# MC33797.net
KiCad netlist of a schematic drawn in Altium Designer
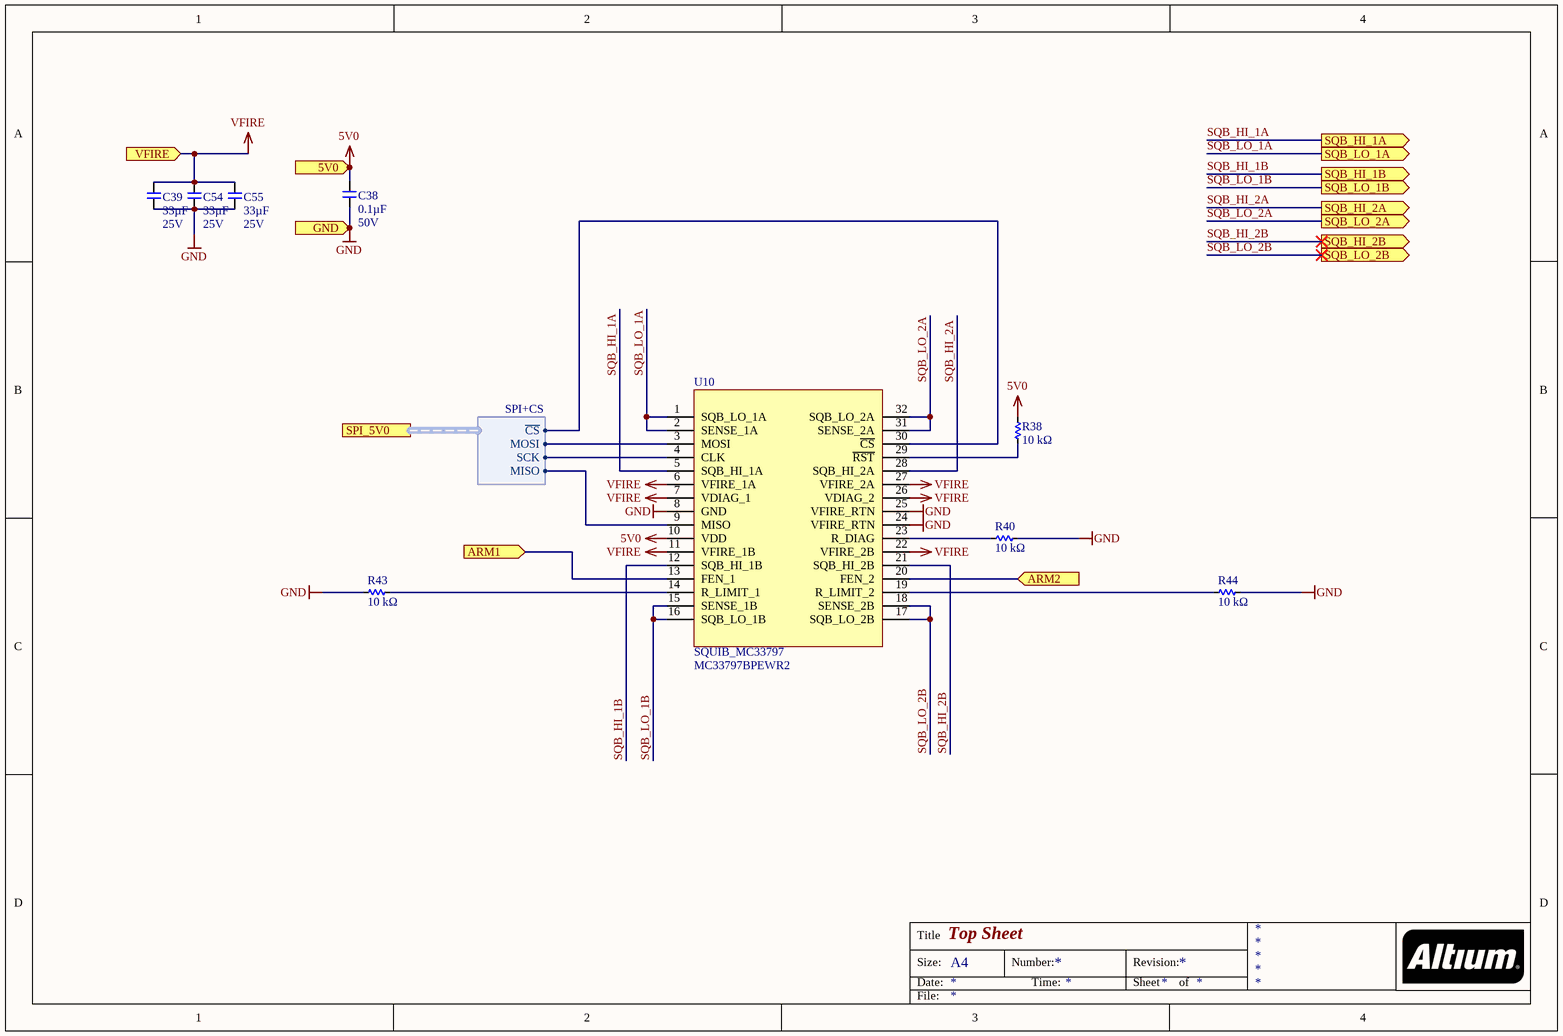
[diagram p0: MC33797.SchDoc]

(export (version "E")
  (design (tool "Eeschema 10.0.6"))
  (components
    (comp (ref "C38")
      (value "__template_cap")
      (footprint "C0603")
      (fields
        (field (name "CAPACITANCE (SHORTHAND)") "0.1µF")
        (field (name "RATED VOLTAGE") "50V")
        (field (name "MANUFACTURER") "Murata Electronics North America")
      )
      (libsource (lib "passives") (part "__template_cap"))
    )
    (comp (ref "C39")
      (value "CAP_33UF_1206_SMD")
      (footprint "C1206")
      (description "100UF SMD CAP CERAMIC")
      (fields
        (field (name "MANUFACTURER") "Murata Electronics North America")
        (field (name "MANUFACTURER PART NUMBER") "GRM31CD80J107ME39L")
        (field (name "CAPACITANCE") "33µF")
        (field (name "VOLTAGE - RATED") "25V")
      )
      (libsource (lib "SSI") (part "CAP_100UF_1206_SMD"))
    )
    (comp (ref "C54")
      (value "CAP_33UF_1206_SMD")
      (footprint "C1206")
      (description "100UF SMD CAP CERAMIC")
      (fields
        (field (name "MANUFACTURER") "Murata Electronics North America")
        (field (name "MANUFACTURER PART NUMBER") "GRM31CD80J107ME39L")
        (field (name "CAPACITANCE") "33µF")
        (field (name "VOLTAGE - RATED") "25V")
      )
      (libsource (lib "SSI") (part "CAP_100UF_1206_SMD"))
    )
    (comp (ref "C55")
      (value "CAP_33UF_1206_SMD")
      (footprint "C1206")
      (description "100UF SMD CAP CERAMIC")
      (fields
        (field (name "MANUFACTURER") "Murata Electronics North America")
        (field (name "MANUFACTURER PART NUMBER") "GRM31CD80J107ME39L")
        (field (name "CAPACITANCE") "33µF")
        (field (name "VOLTAGE - RATED") "25V")
      )
      (libsource (lib "SSI") (part "CAP_100UF_1206_SMD"))
    )
    (comp (ref "R38")
      (value "__template_resistor")
      (footprint "R0603")
      (fields
        (field (name "RESISTANCE") "10 kΩ")
        (field (name "MANUFACTURER PART NUMBER") "RC0603FR-0710KL")
        (field (name "MANUFACTURER") "Yageo")
        (field (name "TOLERANCE") "±1%")
      )
      (libsource (lib "passives") (part "__template_resistor"))
    )
    (comp (ref "R40")
      (value "__template_resistor")
      (footprint "R0603")
      (fields
        (field (name "RESISTANCE") "10 kΩ")
        (field (name "MANUFACTURER PART NUMBER") "RC0603FR-0710KL")
        (field (name "MANUFACTURER") "Yageo")
        (field (name "TOLERANCE") "±1%")
      )
      (libsource (lib "passives") (part "__template_resistor"))
    )
    (comp (ref "R43")
      (value "__template_resistor")
      (footprint "R0603")
      (fields
        (field (name "RESISTANCE") "10 kΩ")
        (field (name "MANUFACTURER PART NUMBER") "RC0603FR-0710KL")
        (field (name "MANUFACTURER") "Yageo")
        (field (name "TOLERANCE") "±1%")
      )
      (libsource (lib "passives") (part "__template_resistor"))
    )
    (comp (ref "R44")
      (value "__template_resistor")
      (footprint "R0603")
      (fields
        (field (name "RESISTANCE") "10 kΩ")
        (field (name "MANUFACTURER PART NUMBER") "RC0603FR-0710KL")
        (field (name "MANUFACTURER") "Yageo")
        (field (name "TOLERANCE") "±1%")
      )
      (libsource (lib "passives") (part "__template_resistor"))
    )
    (comp (ref "U10")
      (value "SQUIB_MC33797")
      (footprint "SOT1762-1")
      (fields
        (field (name "MANUFACTURER") "NXP USA Inc.")
        (field (name "MANUFACTURER PART NUMBER") "MC33797BPEWR2")
      )
      (libsource (lib "SSI") (part "SQUIB_MC33797"))
    )
  )
  (nets
    (net (code "2") (name "/ARM1") (class "Default")
      (node (ref "U10") (pin "13") (pinfunction "FEN_1_13") (pintype "passive"))
    )
    (net (code "3") (name "/ARM2") (class "Default")
      (node (ref "U10") (pin "20") (pinfunction "FEN_2_20") (pintype "passive"))
    )
    (net (code "4") (name "/MISO") (class "Default")
      (node (ref "U10") (pin "9") (pinfunction "MISO_9") (pintype "passive"))
    )
    (net (code "5") (name "/MOSI") (class "Default")
      (node (ref "U10") (pin "3") (pinfunction "MOSI_3") (pintype "passive"))
    )
    (net (code "6") (name "/SCK") (class "Default")
      (node (ref "U10") (pin "4") (pinfunction "CLK_4") (pintype "passive"))
    )
    (net (code "7") (name "/SQB_HI_1A") (class "Default")
      (node (ref "U10") (pin "5") (pinfunction "SQB_HI_1A_5") (pintype "passive"))
    )
    (net (code "8") (name "/SQB_HI_1B") (class "Default")
      (node (ref "U10") (pin "12") (pinfunction "SQB_HI_1B_12") (pintype "passive"))
    )
    (net (code "9") (name "/SQB_HI_2A") (class "Default")
      (node (ref "U10") (pin "28") (pinfunction "SQB_HI_2A_28") (pintype "passive"))
    )
    (net (code "10") (name "/SQB_HI_2B") (class "Default")
      (node (ref "U10") (pin "21") (pinfunction "SQB_HI_2B_21") (pintype "passive+no_connect"))
    )
    (net (code "11") (name "/SQB_LO_1A") (class "Default")
      (node (ref "U10") (pin "1") (pinfunction "SQB_LO_1A_1") (pintype "passive"))
      (node (ref "U10") (pin "2") (pinfunction "SENSE_1A_2") (pintype "passive"))
    )
    (net (code "12") (name "/SQB_LO_1B") (class "Default")
      (node (ref "U10") (pin "15") (pinfunction "SENSE_1B_15") (pintype "passive"))
      (node (ref "U10") (pin "16") (pinfunction "SQB_LO_1B_16") (pintype "passive"))
    )
    (net (code "13") (name "/SQB_LO_2A") (class "Default")
      (node (ref "U10") (pin "31") (pinfunction "SENSE_2A_31") (pintype "passive"))
      (node (ref "U10") (pin "32") (pinfunction "SQB_LO_2A_32") (pintype "passive"))
    )
    (net (code "14") (name "/SQB_LO_2B") (class "Default")
      (node (ref "U10") (pin "17") (pinfunction "SQB_LO_2B_17") (pintype "passive"))
      (node (ref "U10") (pin "18") (pinfunction "SENSE_2B_18") (pintype "passive"))
    )
    (net (code "16") (name "/~{CS}") (class "Default")
      (node (ref "U10") (pin "30") (pinfunction "~{CS}_30") (pintype "passive"))
    )
    (net (code "17") (name "5V0") (class "Default")
      (node (ref "C38") (pin "1") (pintype "passive"))
      (node (ref "R38") (pin "2") (pintype "passive"))
      (node (ref "U10") (pin "10") (pinfunction "VDD_10") (pintype "passive"))
    )
    (net (code "18") (name "GND") (class "Default")
      (node (ref "C38") (pin "2") (pintype "passive"))
      (node (ref "C39") (pin "2") (pintype "passive"))
      (node (ref "C54") (pin "2") (pintype "passive"))
      (node (ref "C55") (pin "2") (pintype "passive"))
      (node (ref "R40") (pin "2") (pintype "passive"))
      (node (ref "R43") (pin "1") (pintype "passive"))
      (node (ref "R44") (pin "2") (pintype "passive"))
      (node (ref "U10") (pin "24") (pinfunction "VFIRE_RTN_24") (pintype "passive"))
      (node (ref "U10") (pin "25") (pinfunction "VFIRE_RTN_25") (pintype "passive"))
      (node (ref "U10") (pin "8") (pinfunction "GND_8") (pintype "passive"))
    )
    (net (code "19") (name "Net-(U10-R_DIAG)") (class "Default")
      (node (ref "R40") (pin "1") (pintype "passive"))
      (node (ref "U10") (pin "23") (pinfunction "R_DIAG_23") (pintype "passive"))
    )
    (net (code "20") (name "Net-(U10-R_LIMIT_1)") (class "Default")
      (node (ref "R43") (pin "2") (pintype "passive"))
      (node (ref "U10") (pin "14") (pinfunction "R_LIMIT_1_14") (pintype "passive"))
    )
    (net (code "21") (name "Net-(U10-R_LIMIT_2)") (class "Default")
      (node (ref "R44") (pin "1") (pintype "passive"))
      (node (ref "U10") (pin "19") (pinfunction "R_LIMIT_2_19") (pintype "passive"))
    )
    (net (code "22") (name "Net-(U10-~{RST})") (class "Default")
      (node (ref "R38") (pin "1") (pintype "passive"))
      (node (ref "U10") (pin "29") (pinfunction "~{RST}_29") (pintype "passive"))
    )
    (net (code "23") (name "VFIRE") (class "Default")
      (node (ref "C39") (pin "1") (pintype "passive"))
      (node (ref "C54") (pin "1") (pintype "passive"))
      (node (ref "C55") (pin "1") (pintype "passive"))
      (node (ref "U10") (pin "11") (pinfunction "VFIRE_1B_11") (pintype "passive"))
      (node (ref "U10") (pin "22") (pinfunction "VFIRE_2B_22") (pintype "passive"))
      (node (ref "U10") (pin "26") (pinfunction "VDIAG_2_26") (pintype "passive"))
      (node (ref "U10") (pin "27") (pinfunction "VFIRE_2A_27") (pintype "passive"))
      (node (ref "U10") (pin "6") (pinfunction "VFIRE_1A_6") (pintype "passive"))
      (node (ref "U10") (pin "7") (pinfunction "VDIAG_1_7") (pintype "passive"))
    )
  )
)
